# K60DN_LQFP100.net
KiCad netlist of a schematic drawn in Altium Designer
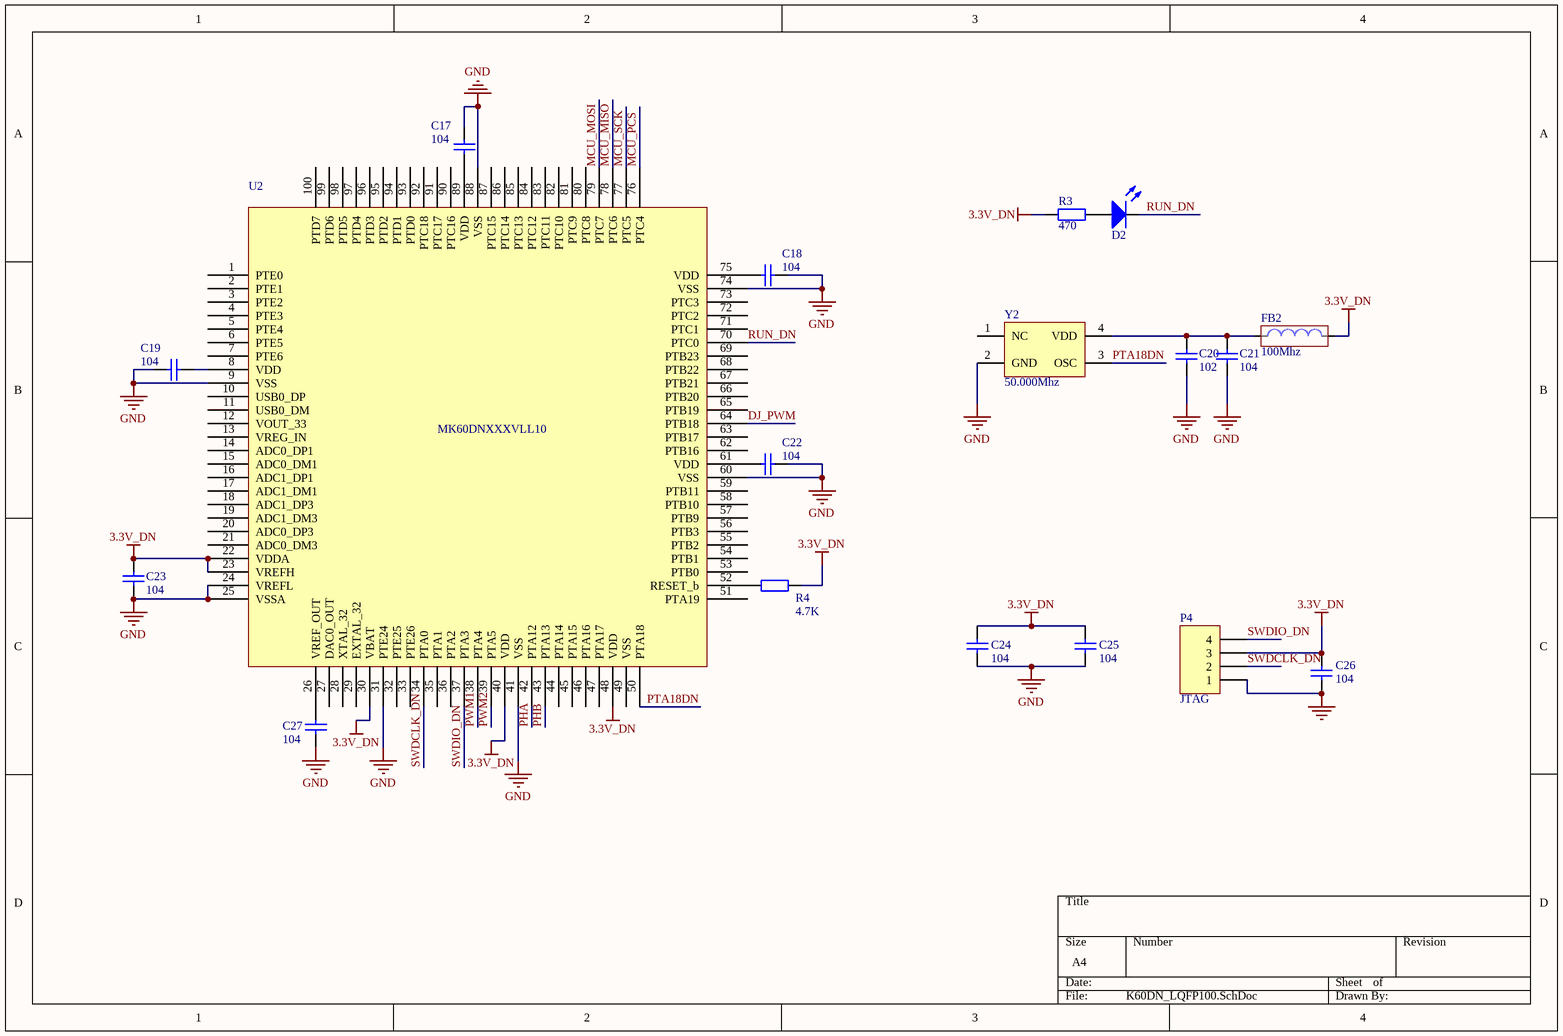
[diagram p0: K60DN_LQFP100.SchDoc]

(export (version "E")
  (design (tool "Eeschema 10.0.6"))
  (components
    (comp (ref "C17") (value "104") (footprint "0805") (libsource (lib "飞思卡尔") (part "Cap")))
    (comp (ref "C18") (value "104") (footprint "0805") (libsource (lib "飞思卡尔") (part "Cap")))
    (comp (ref "C19") (value "104") (footprint "0805") (libsource (lib "飞思卡尔") (part "Cap")))
    (comp (ref "C20") (value "102") (footprint "0805") (libsource (lib "飞思卡尔") (part "Cap")))
    (comp (ref "C21") (value "104") (footprint "0805") (libsource (lib "飞思卡尔") (part "Cap")))
    (comp (ref "C22") (value "104") (footprint "0805") (libsource (lib "飞思卡尔") (part "Cap")))
    (comp (ref "C23") (value "104") (footprint "0805") (libsource (lib "飞思卡尔") (part "Cap")))
    (comp (ref "C24") (value "104") (footprint "0805") (libsource (lib "飞思卡尔") (part "Cap")))
    (comp (ref "C25") (value "104") (footprint "0805") (libsource (lib "飞思卡尔") (part "Cap")))
    (comp (ref "C26") (value "104") (footprint "0805") (libsource (lib "飞思卡尔") (part "Cap")))
    (comp (ref "C27") (value "104") (footprint "0805") (libsource (lib "飞思卡尔") (part "Cap")))
    (comp (ref "D2") (value "Led") (footprint "0805") (libsource (lib "飞思卡尔") (part "Led")))
    (comp (ref "FB2") (value "100Mhz") (footprint "0805") (libsource (lib "飞思卡尔") (part "Inductor")))
    (comp (ref "P4")
      (value "JTAG")
      (footprint "PJ-322")
      (description "Header, 4-Pin")
      (fields (field (name "PUBLISHER") "Altium Limited"))
      (libsource (lib "Miscellaneous Connectors") (part "Header 4"))
    )
    (comp (ref "R3") (value "470") (footprint "0805") (libsource (lib "飞思卡尔") (part "Rest")))
    (comp (ref "R4") (value "4.7K") (footprint "0805") (libsource (lib "飞思卡尔") (part "Rest")))
    (comp (ref "U2")
      (value "MK60DNXXXVLL10")
      (footprint "LQFP-100")
      (libsource (lib "飞思卡尔") (part "K60_100PIN"))
    )
    (comp (ref "Y2") (value "50.000Mhz") (footprint "XTAL-3225") (libsource (lib "飞思卡尔") (part "有源晶振")))
  )
  (nets
    (net (code "1") (name "/DJ_PWM") (class "Default")
      (node (ref "U2") (pin "64") (pinfunction "PTB18_64") (pintype "passive"))
    )
    (net (code "2") (name "/MCU_MISO") (class "Default")
      (node (ref "U2") (pin "78") (pinfunction "PTC6_78") (pintype "passive"))
    )
    (net (code "3") (name "/MCU_MOSI") (class "Default")
      (node (ref "U2") (pin "79") (pinfunction "PTC7_79") (pintype "passive"))
    )
    (net (code "4") (name "/MCU_PCS") (class "Default")
      (node (ref "U2") (pin "76") (pinfunction "PTC4_76") (pintype "passive"))
    )
    (net (code "5") (name "/MCU_SCK") (class "Default")
      (node (ref "U2") (pin "77") (pinfunction "PTC5_77") (pintype "passive"))
    )
    (net (code "6") (name "/PHA") (class "Default")
      (node (ref "U2") (pin "42") (pinfunction "PTA12_42") (pintype "passive"))
    )
    (net (code "7") (name "/PHB") (class "Default")
      (node (ref "U2") (pin "43") (pinfunction "PTA13_43") (pintype "passive"))
    )
    (net (code "8") (name "/PTA18DN") (class "Default")
      (node (ref "U2") (pin "50") (pinfunction "PTA18_50") (pintype "passive"))
      (node (ref "Y2") (pin "3") (pinfunction "OSC_3") (pintype "passive"))
    )
    (net (code "9") (name "/PWM1") (class "Default")
      (node (ref "U2") (pin "38") (pinfunction "PTA4_38") (pintype "passive"))
    )
    (net (code "10") (name "/PWM2") (class "Default")
      (node (ref "U2") (pin "39") (pinfunction "PTA5_39") (pintype "passive"))
    )
    (net (code "11") (name "/RUN_DN") (class "Default")
      (node (ref "D2") (pin "2") (pinfunction "2_2") (pintype "passive"))
      (node (ref "U2") (pin "70") (pinfunction "PTC0_70") (pintype "passive"))
    )
    (net (code "12") (name "/SWDCLK_DN") (class "Default")
      (node (ref "P4") (pin "2") (pinfunction "2_2") (pintype "passive"))
      (node (ref "U2") (pin "34") (pinfunction "PTA0_34") (pintype "passive"))
    )
    (net (code "13") (name "/SWDIO_DN") (class "Default")
      (node (ref "P4") (pin "4") (pinfunction "4_4") (pintype "passive"))
      (node (ref "U2") (pin "37") (pinfunction "PTA3_37") (pintype "passive"))
    )
    (net (code "14") (name "3.3V_DN") (class "Default")
      (node (ref "C23") (pin "2") (pinfunction "2_2") (pintype "passive"))
      (node (ref "C24") (pin "2") (pinfunction "2_2") (pintype "passive"))
      (node (ref "C25") (pin "2") (pinfunction "2_2") (pintype "passive"))
      (node (ref "C26") (pin "1") (pinfunction "1_1") (pintype "passive"))
      (node (ref "FB2") (pin "2") (pinfunction "2_2") (pintype "passive"))
      (node (ref "P4") (pin "3") (pinfunction "3_3") (pintype "passive"))
      (node (ref "R3") (pin "1") (pinfunction "1_1") (pintype "passive"))
      (node (ref "R4") (pin "2") (pinfunction "2_2") (pintype "passive"))
      (node (ref "U2") (pin "22") (pinfunction "VDDA_22") (pintype "passive"))
      (node (ref "U2") (pin "23") (pinfunction "VREFH_23") (pintype "passive"))
      (node (ref "U2") (pin "30") (pinfunction "VBAT_30") (pintype "passive"))
      (node (ref "U2") (pin "40") (pinfunction "VDD_40") (pintype "passive"))
      (node (ref "U2") (pin "48") (pinfunction "VDD_48") (pintype "passive"))
    )
    (net (code "15") (name "GND") (class "Default")
      (node (ref "C17") (pin "2") (pinfunction "2_2") (pintype "passive"))
      (node (ref "C18") (pin "1") (pinfunction "1_1") (pintype "passive"))
      (node (ref "C19") (pin "1") (pinfunction "1_1") (pintype "passive"))
      (node (ref "C20") (pin "1") (pinfunction "1_1") (pintype "passive"))
      (node (ref "C21") (pin "1") (pinfunction "1_1") (pintype "passive"))
      (node (ref "C22") (pin "1") (pinfunction "1_1") (pintype "passive"))
      (node (ref "C23") (pin "1") (pinfunction "1_1") (pintype "passive"))
      (node (ref "C24") (pin "1") (pinfunction "1_1") (pintype "passive"))
      (node (ref "C25") (pin "1") (pinfunction "1_1") (pintype "passive"))
      (node (ref "C26") (pin "2") (pinfunction "2_2") (pintype "passive"))
      (node (ref "C27") (pin "1") (pinfunction "1_1") (pintype "passive"))
      (node (ref "P4") (pin "1") (pinfunction "1_1") (pintype "passive"))
      (node (ref "U2") (pin "24") (pinfunction "VREFL_24") (pintype "passive"))
      (node (ref "U2") (pin "25") (pinfunction "VSSA_25") (pintype "passive"))
      (node (ref "U2") (pin "31") (pinfunction "PTE24_31") (pintype "passive"))
      (node (ref "U2") (pin "41") (pinfunction "VSS_41") (pintype "passive"))
      (node (ref "U2") (pin "60") (pinfunction "VSS_60") (pintype "passive"))
      (node (ref "U2") (pin "74") (pinfunction "VSS_74") (pintype "passive"))
      (node (ref "U2") (pin "88") (pinfunction "VSS_88") (pintype "passive"))
      (node (ref "U2") (pin "9") (pinfunction "VSS_9") (pintype "passive"))
      (node (ref "Y2") (pin "2") (pinfunction "GND_2") (pintype "passive"))
    )
    (net (code "16") (name "Net-(C17-Pad1)") (class "Default")
      (node (ref "C17") (pin "1") (pinfunction "1_1") (pintype "passive"))
      (node (ref "U2") (pin "89") (pinfunction "VDD_89") (pintype "passive"))
    )
    (net (code "17") (name "Net-(C18-Pad2)") (class "Default")
      (node (ref "C18") (pin "2") (pinfunction "2_2") (pintype "passive"))
      (node (ref "U2") (pin "75") (pinfunction "VDD_75") (pintype "passive"))
    )
    (net (code "18") (name "Net-(C19-Pad2)") (class "Default")
      (node (ref "C19") (pin "2") (pinfunction "2_2") (pintype "passive"))
      (node (ref "U2") (pin "8") (pinfunction "VDD_8") (pintype "passive"))
    )
    (net (code "19") (name "Net-(C22-Pad2)") (class "Default")
      (node (ref "C22") (pin "2") (pinfunction "2_2") (pintype "passive"))
      (node (ref "U2") (pin "61") (pinfunction "VDD_61") (pintype "passive"))
    )
    (net (code "20") (name "Net-(D2-Pad1)") (class "Default")
      (node (ref "D2") (pin "1") (pinfunction "1_1") (pintype "passive"))
      (node (ref "R3") (pin "2") (pinfunction "2_2") (pintype "passive"))
    )
    (net (code "21") (name "Net-(U2-RESET_b)") (class "Default")
      (node (ref "R4") (pin "1") (pinfunction "1_1") (pintype "passive"))
      (node (ref "U2") (pin "52") (pinfunction "RESET_b_52") (pintype "passive"))
    )
    (net (code "22") (name "Net-(U2-VREF_OUT)") (class "Default")
      (node (ref "C27") (pin "2") (pinfunction "2_2") (pintype "passive"))
      (node (ref "U2") (pin "26") (pinfunction "VREF_OUT_26") (pintype "passive"))
    )
    (net (code "23") (name "Net-(Y2-VDD)") (class "Default")
      (node (ref "C20") (pin "2") (pinfunction "2_2") (pintype "passive"))
      (node (ref "C21") (pin "2") (pinfunction "2_2") (pintype "passive"))
      (node (ref "FB2") (pin "1") (pinfunction "1_1") (pintype "passive"))
      (node (ref "Y2") (pin "4") (pinfunction "VDD_4") (pintype "passive"))
    )
    (net (code "24") (name "unconnected-(U2-ADC0_DM1-Pad15)") (class "Default")
      (node (ref "U2") (pin "15") (pinfunction "ADC0_DM1_15") (pintype "passive"))
    )
    (net (code "25") (name "unconnected-(U2-ADC0_DM3-Pad21)") (class "Default")
      (node (ref "U2") (pin "21") (pinfunction "ADC0_DM3_21") (pintype "passive"))
    )
    (net (code "26") (name "unconnected-(U2-ADC0_DP1-Pad14)") (class "Default")
      (node (ref "U2") (pin "14") (pinfunction "ADC0_DP1_14") (pintype "passive"))
    )
    (net (code "27") (name "unconnected-(U2-ADC0_DP3-Pad20)") (class "Default")
      (node (ref "U2") (pin "20") (pinfunction "ADC0_DP3_20") (pintype "passive"))
    )
    (net (code "28") (name "unconnected-(U2-ADC1_DM1-Pad17)") (class "Default")
      (node (ref "U2") (pin "17") (pinfunction "ADC1_DM1_17") (pintype "passive"))
    )
    (net (code "29") (name "unconnected-(U2-ADC1_DM3-Pad19)") (class "Default")
      (node (ref "U2") (pin "19") (pinfunction "ADC1_DM3_19") (pintype "passive"))
    )
    (net (code "30") (name "unconnected-(U2-ADC1_DP1-Pad16)") (class "Default")
      (node (ref "U2") (pin "16") (pinfunction "ADC1_DP1_16") (pintype "passive"))
    )
    (net (code "31") (name "unconnected-(U2-ADC1_DP3-Pad18)") (class "Default")
      (node (ref "U2") (pin "18") (pinfunction "ADC1_DP3_18") (pintype "passive"))
    )
    (net (code "32") (name "unconnected-(U2-DAC0_OUT-Pad27)") (class "Default")
      (node (ref "U2") (pin "27") (pinfunction "DAC0_OUT_27") (pintype "passive"))
    )
    (net (code "33") (name "unconnected-(U2-EXTAL_32-Pad29)") (class "Default")
      (node (ref "U2") (pin "29") (pinfunction "EXTAL_32_29") (pintype "passive"))
    )
    (net (code "34") (name "unconnected-(U2-PTA1-Pad35)") (class "Default")
      (node (ref "U2") (pin "35") (pinfunction "PTA1_35") (pintype "passive"))
    )
    (net (code "35") (name "unconnected-(U2-PTA2-Pad36)") (class "Default")
      (node (ref "U2") (pin "36") (pinfunction "PTA2_36") (pintype "passive"))
    )
    (net (code "36") (name "unconnected-(U2-PTA14-Pad44)") (class "Default")
      (node (ref "U2") (pin "44") (pinfunction "PTA14_44") (pintype "passive"))
    )
    (net (code "37") (name "unconnected-(U2-PTA15-Pad45)") (class "Default")
      (node (ref "U2") (pin "45") (pinfunction "PTA15_45") (pintype "passive"))
    )
    (net (code "38") (name "unconnected-(U2-PTA16-Pad46)") (class "Default")
      (node (ref "U2") (pin "46") (pinfunction "PTA16_46") (pintype "passive"))
    )
    (net (code "39") (name "unconnected-(U2-PTA17-Pad47)") (class "Default")
      (node (ref "U2") (pin "47") (pinfunction "PTA17_47") (pintype "passive"))
    )
    (net (code "40") (name "unconnected-(U2-PTA19-Pad51)") (class "Default")
      (node (ref "U2") (pin "51") (pinfunction "PTA19_51") (pintype "passive"))
    )
    (net (code "41") (name "unconnected-(U2-PTB0-Pad53)") (class "Default")
      (node (ref "U2") (pin "53") (pinfunction "PTB0_53") (pintype "passive"))
    )
    (net (code "42") (name "unconnected-(U2-PTB1-Pad54)") (class "Default")
      (node (ref "U2") (pin "54") (pinfunction "PTB1_54") (pintype "passive"))
    )
    (net (code "43") (name "unconnected-(U2-PTB2-Pad55)") (class "Default")
      (node (ref "U2") (pin "55") (pinfunction "PTB2_55") (pintype "passive"))
    )
    (net (code "44") (name "unconnected-(U2-PTB3-Pad56)") (class "Default")
      (node (ref "U2") (pin "56") (pinfunction "PTB3_56") (pintype "passive"))
    )
    (net (code "45") (name "unconnected-(U2-PTB9-Pad57)") (class "Default")
      (node (ref "U2") (pin "57") (pinfunction "PTB9_57") (pintype "passive"))
    )
    (net (code "46") (name "unconnected-(U2-PTB10-Pad58)") (class "Default")
      (node (ref "U2") (pin "58") (pinfunction "PTB10_58") (pintype "passive"))
    )
    (net (code "47") (name "unconnected-(U2-PTB11-Pad59)") (class "Default")
      (node (ref "U2") (pin "59") (pinfunction "PTB11_59") (pintype "passive"))
    )
    (net (code "48") (name "unconnected-(U2-PTB16-Pad62)") (class "Default")
      (node (ref "U2") (pin "62") (pinfunction "PTB16_62") (pintype "passive"))
    )
    (net (code "49") (name "unconnected-(U2-PTB17-Pad63)") (class "Default")
      (node (ref "U2") (pin "63") (pinfunction "PTB17_63") (pintype "passive"))
    )
    (net (code "50") (name "unconnected-(U2-PTB19-Pad65)") (class "Default")
      (node (ref "U2") (pin "65") (pinfunction "PTB19_65") (pintype "passive"))
    )
    (net (code "51") (name "unconnected-(U2-PTB20-Pad66)") (class "Default")
      (node (ref "U2") (pin "66") (pinfunction "PTB20_66") (pintype "passive"))
    )
    (net (code "52") (name "unconnected-(U2-PTB21-Pad67)") (class "Default")
      (node (ref "U2") (pin "67") (pinfunction "PTB21_67") (pintype "passive"))
    )
    (net (code "53") (name "unconnected-(U2-PTB22-Pad68)") (class "Default")
      (node (ref "U2") (pin "68") (pinfunction "PTB22_68") (pintype "passive"))
    )
    (net (code "54") (name "unconnected-(U2-PTB23-Pad69)") (class "Default")
      (node (ref "U2") (pin "69") (pinfunction "PTB23_69") (pintype "passive"))
    )
    (net (code "55") (name "unconnected-(U2-PTC1-Pad71)") (class "Default")
      (node (ref "U2") (pin "71") (pinfunction "PTC1_71") (pintype "passive"))
    )
    (net (code "56") (name "unconnected-(U2-PTC2-Pad72)") (class "Default")
      (node (ref "U2") (pin "72") (pinfunction "PTC2_72") (pintype "passive"))
    )
    (net (code "57") (name "unconnected-(U2-PTC3-Pad73)") (class "Default")
      (node (ref "U2") (pin "73") (pinfunction "PTC3_73") (pintype "passive"))
    )
    (net (code "58") (name "unconnected-(U2-PTC8-Pad80)") (class "Default")
      (node (ref "U2") (pin "80") (pinfunction "PTC8_80") (pintype "passive"))
    )
    (net (code "59") (name "unconnected-(U2-PTC9-Pad81)") (class "Default")
      (node (ref "U2") (pin "81") (pinfunction "PTC9_81") (pintype "passive"))
    )
    (net (code "60") (name "unconnected-(U2-PTC10-Pad82)") (class "Default")
      (node (ref "U2") (pin "82") (pinfunction "PTC10_82") (pintype "passive"))
    )
    (net (code "61") (name "unconnected-(U2-PTC11-Pad83)") (class "Default")
      (node (ref "U2") (pin "83") (pinfunction "PTC11_83") (pintype "passive"))
    )
    (net (code "62") (name "unconnected-(U2-PTC12-Pad84)") (class "Default")
      (node (ref "U2") (pin "84") (pinfunction "PTC12_84") (pintype "passive"))
    )
    (net (code "63") (name "unconnected-(U2-PTC13-Pad85)") (class "Default")
      (node (ref "U2") (pin "85") (pinfunction "PTC13_85") (pintype "passive"))
    )
    (net (code "64") (name "unconnected-(U2-PTC14-Pad86)") (class "Default")
      (node (ref "U2") (pin "86") (pinfunction "PTC14_86") (pintype "passive"))
    )
    (net (code "65") (name "unconnected-(U2-PTC15-Pad87)") (class "Default")
      (node (ref "U2") (pin "87") (pinfunction "PTC15_87") (pintype "passive"))
    )
    (net (code "66") (name "unconnected-(U2-PTC16-Pad90)") (class "Default")
      (node (ref "U2") (pin "90") (pinfunction "PTC16_90") (pintype "passive"))
    )
    (net (code "67") (name "unconnected-(U2-PTC17-Pad91)") (class "Default")
      (node (ref "U2") (pin "91") (pinfunction "PTC17_91") (pintype "passive"))
    )
    (net (code "68") (name "unconnected-(U2-PTC18-Pad92)") (class "Default")
      (node (ref "U2") (pin "92") (pinfunction "PTC18_92") (pintype "passive"))
    )
    (net (code "69") (name "unconnected-(U2-PTD0-Pad93)") (class "Default")
      (node (ref "U2") (pin "93") (pinfunction "PTD0_93") (pintype "passive"))
    )
    (net (code "70") (name "unconnected-(U2-PTD1-Pad94)") (class "Default")
      (node (ref "U2") (pin "94") (pinfunction "PTD1_94") (pintype "passive"))
    )
    (net (code "71") (name "unconnected-(U2-PTD2-Pad95)") (class "Default")
      (node (ref "U2") (pin "95") (pinfunction "PTD2_95") (pintype "passive"))
    )
    (net (code "72") (name "unconnected-(U2-PTD3-Pad96)") (class "Default")
      (node (ref "U2") (pin "96") (pinfunction "PTD3_96") (pintype "passive"))
    )
    (net (code "73") (name "unconnected-(U2-PTD4-Pad97)") (class "Default")
      (node (ref "U2") (pin "97") (pinfunction "PTD4_97") (pintype "passive"))
    )
    (net (code "74") (name "unconnected-(U2-PTD5-Pad98)") (class "Default")
      (node (ref "U2") (pin "98") (pinfunction "PTD5_98") (pintype "passive"))
    )
    (net (code "75") (name "unconnected-(U2-PTD6-Pad99)") (class "Default")
      (node (ref "U2") (pin "99") (pinfunction "PTD6_99") (pintype "passive"))
    )
    (net (code "76") (name "unconnected-(U2-PTD7-Pad100)") (class "Default")
      (node (ref "U2") (pin "100") (pinfunction "PTD7_100") (pintype "passive"))
    )
    (net (code "77") (name "unconnected-(U2-PTE0-Pad1)") (class "Default")
      (node (ref "U2") (pin "1") (pinfunction "PTE0_1") (pintype "passive"))
    )
    (net (code "78") (name "unconnected-(U2-PTE1-Pad2)") (class "Default")
      (node (ref "U2") (pin "2") (pinfunction "PTE1_2") (pintype "passive"))
    )
    (net (code "79") (name "unconnected-(U2-PTE2-Pad3)") (class "Default")
      (node (ref "U2") (pin "3") (pinfunction "PTE2_3") (pintype "passive"))
    )
    (net (code "80") (name "unconnected-(U2-PTE3-Pad4)") (class "Default")
      (node (ref "U2") (pin "4") (pinfunction "PTE3_4") (pintype "passive"))
    )
    (net (code "81") (name "unconnected-(U2-PTE4-Pad5)") (class "Default")
      (node (ref "U2") (pin "5") (pinfunction "PTE4_5") (pintype "passive"))
    )
    (net (code "82") (name "unconnected-(U2-PTE5-Pad6)") (class "Default")
      (node (ref "U2") (pin "6") (pinfunction "PTE5_6") (pintype "passive"))
    )
    (net (code "83") (name "unconnected-(U2-PTE6-Pad7)") (class "Default")
      (node (ref "U2") (pin "7") (pinfunction "PTE6_7") (pintype "passive"))
    )
    (net (code "84") (name "unconnected-(U2-PTE25-Pad32)") (class "Default")
      (node (ref "U2") (pin "32") (pinfunction "PTE25_32") (pintype "passive"))
    )
    (net (code "85") (name "unconnected-(U2-PTE26-Pad33)") (class "Default")
      (node (ref "U2") (pin "33") (pinfunction "PTE26_33") (pintype "passive"))
    )
    (net (code "86") (name "unconnected-(U2-USB0_DM-Pad11)") (class "Default")
      (node (ref "U2") (pin "11") (pinfunction "USB0_DM_11") (pintype "passive"))
    )
    (net (code "87") (name "unconnected-(U2-USB0_DP-Pad10)") (class "Default")
      (node (ref "U2") (pin "10") (pinfunction "USB0_DP_10") (pintype "passive"))
    )
    (net (code "88") (name "unconnected-(U2-VOUT_33-Pad12)") (class "Default")
      (node (ref "U2") (pin "12") (pinfunction "VOUT_33_12") (pintype "passive"))
    )
    (net (code "89") (name "unconnected-(U2-VREG_IN-Pad13)") (class "Default")
      (node (ref "U2") (pin "13") (pinfunction "VREG_IN_13") (pintype "passive"))
    )
    (net (code "90") (name "unconnected-(U2-VSS-Pad49)") (class "Default")
      (node (ref "U2") (pin "49") (pinfunction "VSS_49") (pintype "passive"))
    )
    (net (code "91") (name "unconnected-(U2-XTAL_32-Pad28)") (class "Default")
      (node (ref "U2") (pin "28") (pinfunction "XTAL_32_28") (pintype "passive"))
    )
    (net (code "92") (name "unconnected-(Y2-NC-Pad1)") (class "Default")
      (node (ref "Y2") (pin "1") (pinfunction "NC_1") (pintype "passive"))
    )
  )
)
